# random_generator_2.net
KiCad netlist of a schematic drawn in EAGLE
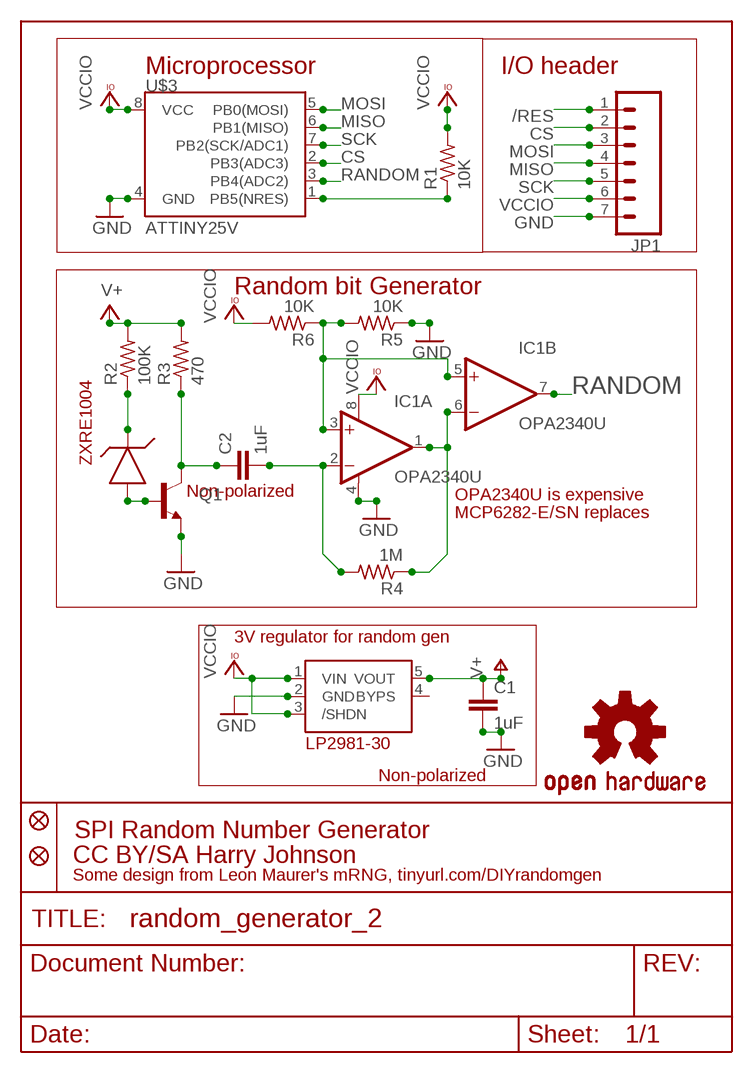
[diagram p0: schematic, sheet 1]

(export (version "E")
  (design (tool "Eeschema 10.0.6"))
  (components
    (comp (ref "C1")
      (value "1uF")
      (footprint "eagle-import:0805")
      (libsource (lib "eagle-import") (part "CAP0805"))
    )
    (comp (ref "C2")
      (value "1uF")
      (footprint "eagle-import:0805")
      (libsource (lib "eagle-import") (part "CAP0805"))
    )
    (comp (ref "IC1")
      (value "OPA2340U")
      (footprint "eagle-import:SO08")
      (fields (field (name "MF") "TEXAS INSTRUMENTS") (field (name "MPN") "OPA2340UA"))
      (libsource (lib "eagle-import") (part "OPA2340U"))
    )
    (comp (ref "JP1")
      (value "M07")
      (footprint "eagle-import:1X07")
      (libsource (lib "eagle-import") (part "M07"))
    )
    (comp (ref "JP2")
      (value "FIDUCIALUFIDUCIAL")
      (footprint "eagle-import:MICRO-FIDUCIAL")
      (libsource (lib "eagle-import") (part "FIDUCIALUFIDUCIAL"))
    )
    (comp (ref "JP3")
      (value "FIDUCIALUFIDUCIAL")
      (footprint "eagle-import:MICRO-FIDUCIAL")
      (libsource (lib "eagle-import") (part "FIDUCIALUFIDUCIAL"))
    )
    (comp (ref "Q1")
      (value "TRANSISTOR_NPNSOT23")
      (footprint "eagle-import:SOT23")
      (libsource (lib "eagle-import") (part "TRANSISTOR_NPNSOT23"))
    )
    (comp (ref "R1")
      (value "10K")
      (footprint "eagle-import:R0805")
      (libsource (lib "eagle-import") (part "R-US_R0805"))
    )
    (comp (ref "R2")
      (value "100K")
      (footprint "eagle-import:R0805")
      (libsource (lib "eagle-import") (part "R-US_R0805"))
    )
    (comp (ref "R3")
      (value "470")
      (footprint "eagle-import:R0805")
      (libsource (lib "eagle-import") (part "R-US_R0805"))
    )
    (comp (ref "R4")
      (value "1M")
      (footprint "eagle-import:R0805")
      (libsource (lib "eagle-import") (part "R-US_R0805"))
    )
    (comp (ref "R5")
      (value "10K")
      (footprint "eagle-import:R0805")
      (libsource (lib "eagle-import") (part "R-US_R0805"))
    )
    (comp (ref "R6")
      (value "10K")
      (footprint "eagle-import:R0805")
      (libsource (lib "eagle-import") (part "R-US_R0805"))
    )
    (comp (ref "U$1")
      (value "ZXRE1004FFTA")
      (footprint "eagle-import:SOT23")
      (libsource (lib "eagle-import") (part "ZXRE1004FFTA"))
    )
    (comp (ref "U$2")
      (value "TC1014")
      (footprint "eagle-import:SOT23-5L")
      (libsource (lib "eagle-import") (part "TC1014"))
    )
    (comp (ref "U$3")
      (value "ATTINY25V")
      (footprint "eagle-import:SO08-EIAJ")
      (libsource (lib "eagle-import") (part "ATTINY45"))
    )
    (comp (ref "U$4")
      (value "OSHW-LOGOS")
      (footprint "eagle-import:OSHW-LOGO-S")
      (libsource (lib "eagle-import") (part "OSHW-LOGOS"))
    )
  )
  (nets
    (net (code "1") (name "/CS") (class "Default")
      (node (ref "JP1") (pin "2") (pinfunction "2_2") (pintype "passive"))
      (node (ref "U$3") (pin "2") (pinfunction "PB3(ADC3)_2") (pintype "bidirectional"))
    )
    (net (code "2") (name "/MISO") (class "Default")
      (node (ref "JP1") (pin "4") (pinfunction "4_4") (pintype "passive"))
      (node (ref "U$3") (pin "6") (pinfunction "PB1(MISO)_6") (pintype "bidirectional"))
    )
    (net (code "3") (name "/MOSI") (class "Default")
      (node (ref "JP1") (pin "3") (pinfunction "3_3") (pintype "passive"))
      (node (ref "U$3") (pin "5") (pinfunction "PB0(MOSI)_5") (pintype "bidirectional"))
    )
    (net (code "4") (name "/RANDOM") (class "Default")
      (node (ref "IC1") (pin "7") (pinfunction "OUT_7") (pintype "output"))
      (node (ref "U$3") (pin "3") (pinfunction "PB4(ADC2)_3") (pintype "bidirectional"))
    )
    (net (code "5") (name "/SCK") (class "Default")
      (node (ref "JP1") (pin "5") (pinfunction "5_5") (pintype "passive"))
      (node (ref "U$3") (pin "7") (pinfunction "PB2(SCK/ADC1)_7") (pintype "bidirectional"))
    )
    (net (code "6") (name "/{slash}RES") (class "Default")
      (node (ref "JP1") (pin "1") (pinfunction "1_1") (pintype "passive"))
      (node (ref "R1") (pin "1") (pinfunction "1_1") (pintype "passive"))
      (node (ref "U$3") (pin "1") (pinfunction "PB5(NRES)_1") (pintype "bidirectional"))
    )
    (net (code "7") (name "GND") (class "Default")
      (node (ref "C1") (pin "2") (pinfunction "2_2") (pintype "passive"))
      (node (ref "IC1") (pin "4") (pinfunction "V-_4") (pintype "power_in"))
      (node (ref "JP1") (pin "7") (pinfunction "7_7") (pintype "passive"))
      (node (ref "Q1") (pin "2") (pinfunction "E_2") (pintype "passive"))
      (node (ref "R5") (pin "1") (pinfunction "1_1") (pintype "passive"))
      (node (ref "U$2") (pin "2") (pinfunction "GND_2") (pintype "bidirectional"))
      (node (ref "U$3") (pin "4") (pinfunction "GND_4") (pintype "bidirectional"))
    )
    (net (code "8") (name "Net-(IC1A-+IN)") (class "Default")
      (node (ref "IC1") (pin "3") (pinfunction "+IN_3") (pintype "input"))
      (node (ref "IC1") (pin "5") (pinfunction "+IN_5") (pintype "input"))
      (node (ref "R5") (pin "2") (pinfunction "2_2") (pintype "passive"))
      (node (ref "R6") (pin "1") (pinfunction "1_1") (pintype "passive"))
    )
    (net (code "9") (name "Net-(IC1A--IN)") (class "Default")
      (node (ref "C2") (pin "2") (pinfunction "2_2") (pintype "passive"))
      (node (ref "IC1") (pin "2") (pinfunction "-IN_2") (pintype "input"))
      (node (ref "R4") (pin "2") (pinfunction "2_2") (pintype "passive"))
    )
    (net (code "10") (name "Net-(IC1A-OUT)") (class "Default")
      (node (ref "IC1") (pin "1") (pinfunction "OUT_1") (pintype "output"))
      (node (ref "IC1") (pin "6") (pinfunction "-IN_6") (pintype "input"))
      (node (ref "R4") (pin "1") (pinfunction "1_1") (pintype "passive"))
    )
    (net (code "11") (name "Net-(Q1-B)") (class "Default")
      (node (ref "Q1") (pin "1") (pinfunction "B_1") (pintype "passive"))
      (node (ref "U$1") (pin "2") (pinfunction "A_2") (pintype "bidirectional"))
    )
    (net (code "12") (name "Net-(Q1-C)") (class "Default")
      (node (ref "C2") (pin "1") (pinfunction "1_1") (pintype "passive"))
      (node (ref "Q1") (pin "3") (pinfunction "C_3") (pintype "passive"))
      (node (ref "R3") (pin "1") (pinfunction "1_1") (pintype "passive"))
    )
    (net (code "13") (name "Net-(U$1-K)") (class "Default")
      (node (ref "R2") (pin "1") (pinfunction "1_1") (pintype "passive"))
      (node (ref "U$1") (pin "1") (pinfunction "K_1") (pintype "bidirectional"))
    )
    (net (code "14") (name "V+") (class "Default")
      (node (ref "C1") (pin "1") (pinfunction "1_1") (pintype "passive"))
      (node (ref "R2") (pin "2") (pinfunction "2_2") (pintype "passive"))
      (node (ref "R3") (pin "2") (pinfunction "2_2") (pintype "passive"))
      (node (ref "U$2") (pin "5") (pinfunction "VOUT_5") (pintype "bidirectional"))
    )
    (net (code "15") (name "VCCIO") (class "Default")
      (node (ref "IC1") (pin "8") (pinfunction "V+_8") (pintype "power_in"))
      (node (ref "JP1") (pin "6") (pinfunction "6_6") (pintype "passive"))
      (node (ref "R1") (pin "2") (pinfunction "2_2") (pintype "passive"))
      (node (ref "R6") (pin "2") (pinfunction "2_2") (pintype "passive"))
      (node (ref "U$2") (pin "1") (pinfunction "VIN_1") (pintype "bidirectional"))
      (node (ref "U$2") (pin "3") (pinfunction "/SHDN_3") (pintype "bidirectional"))
      (node (ref "U$3") (pin "8") (pinfunction "VCC_8") (pintype "bidirectional"))
    )
    (net (code "16") (name "unconnected-(U$2-BYPS-Pad4)") (class "Default")
      (node (ref "U$2") (pin "4") (pinfunction "BYPS_4") (pintype "bidirectional"))
    )
  )
)
